# YOTSUBA_GNSS-receiver_Orion_ver_1_5_2.net
KiCad netlist of a schematic drawn in EAGLE
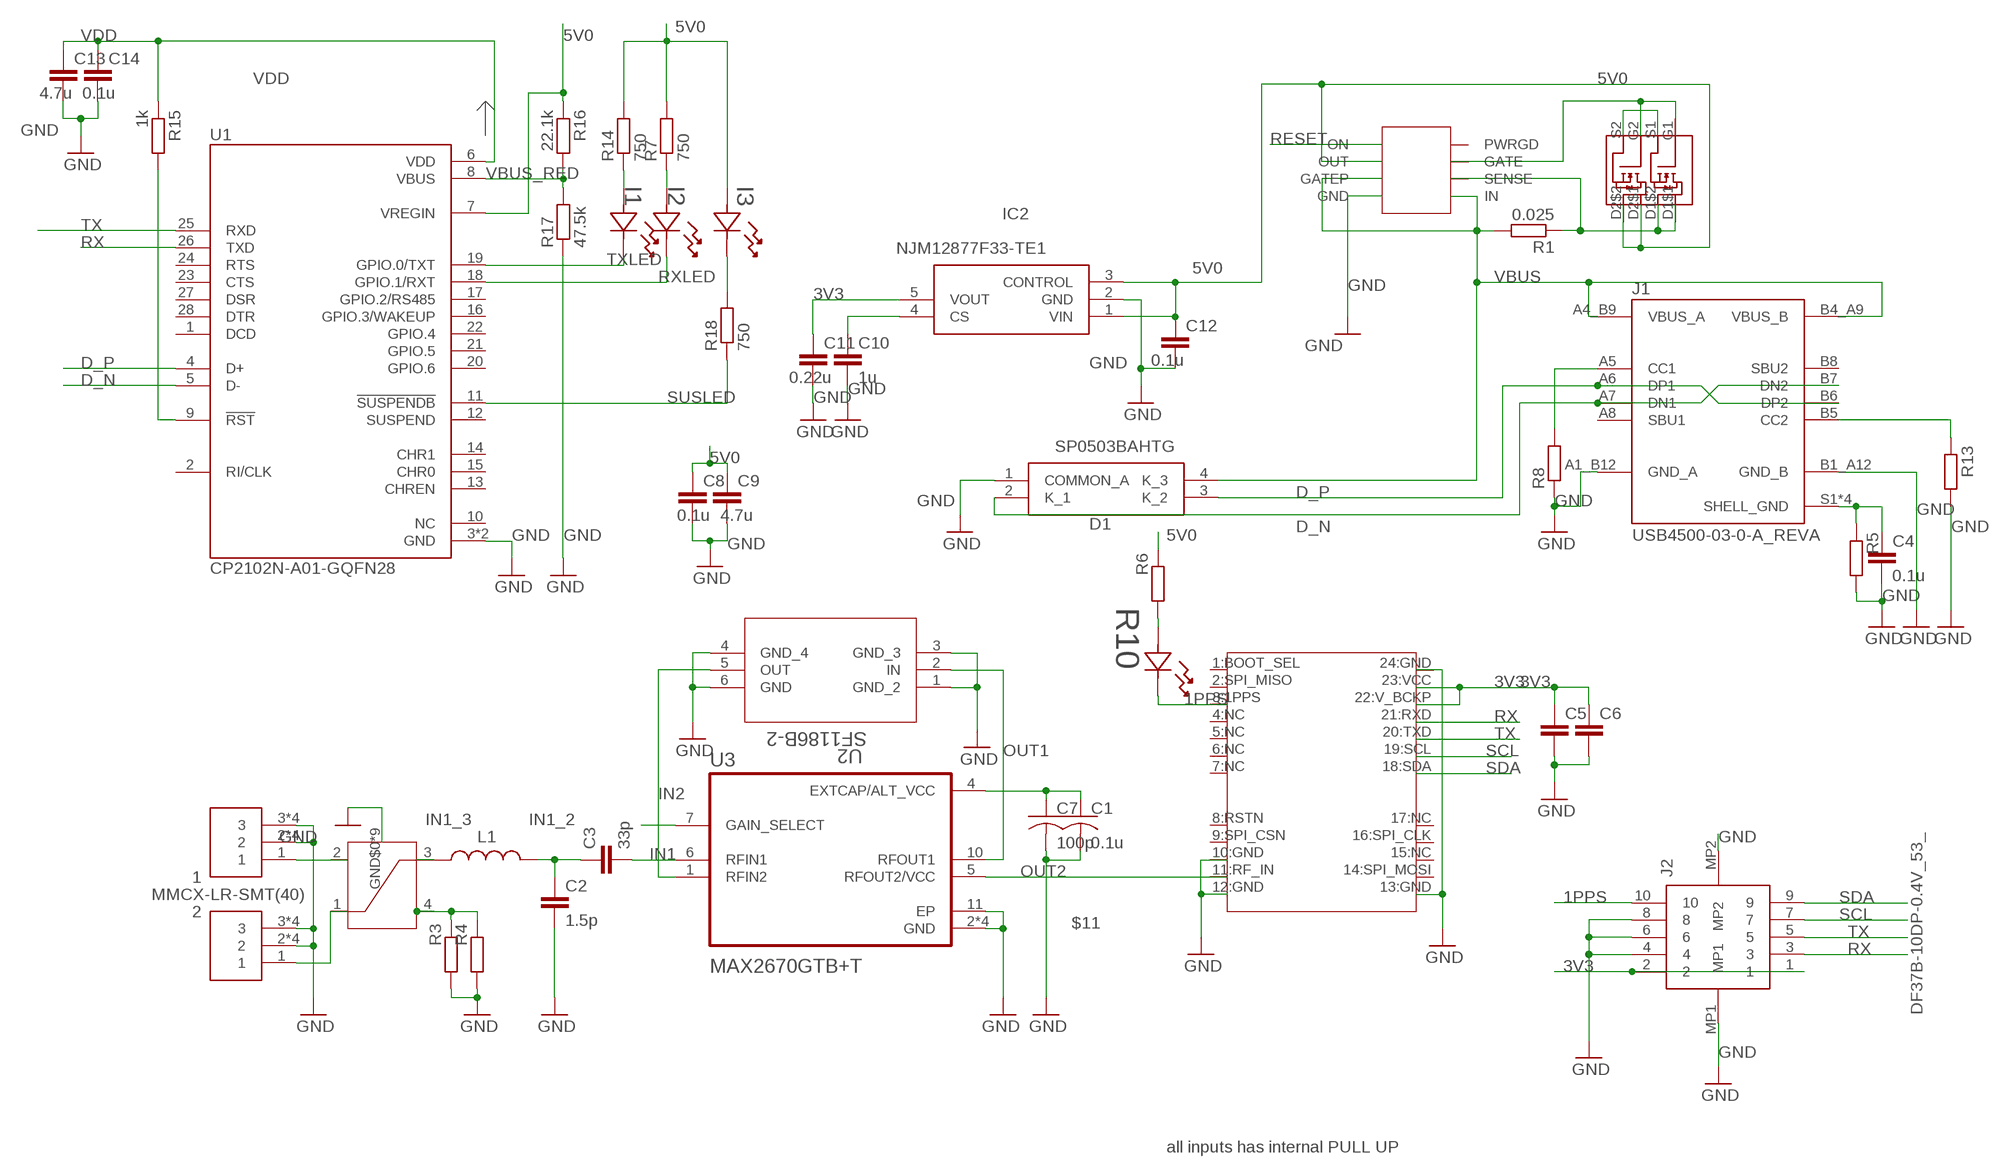
[diagram p0: schematic, sheet 1]

(export (version "E")
  (design (tool "Eeschema 10.0.6"))
  (components
    (comp (ref "1")
      (value "MMCX-LR-SMT(40)")
      (footprint "eagle-import:MMCX-LR-SMT(40)")
      (libsource (lib "eagle-import") (part "MMCX-LR-SMT(40)"))
    )
    (comp (ref "2")
      (value "MMCX-LR-SMT(40)")
      (footprint "eagle-import:MMCX-LR-SMT(40)")
      (libsource (lib "eagle-import") (part "MMCX-LR-SMT(40)"))
    )
    (comp (ref "C1")
      (value "0.1u")
      (footprint "eagle-import:C1608_OS")
      (libsource (lib "eagle-import") (part "C-US"))
    )
    (comp (ref "C2")
      (value "1.5p")
      (footprint "eagle-import:C1608")
      (libsource (lib "eagle-import") (part "C-EUC1608"))
    )
    (comp (ref "C3")
      (value "33p")
      (footprint "eagle-import:C1608")
      (libsource (lib "eagle-import") (part "C-EUC1608"))
    )
    (comp (ref "C4")
      (value "0.1u")
      (footprint "eagle-import:C1608")
      (libsource (lib "eagle-import") (part "C-EUC1608"))
    )
    (comp (ref "C5")
      (value "C-EUC1608")
      (footprint "eagle-import:C1608")
      (libsource (lib "eagle-import") (part "C-EUC1608"))
    )
    (comp (ref "C6")
      (value "C-EUC1608")
      (footprint "eagle-import:C1608")
      (libsource (lib "eagle-import") (part "C-EUC1608"))
    )
    (comp (ref "C7")
      (value "100p")
      (footprint "eagle-import:C1608_OS")
      (libsource (lib "eagle-import") (part "C-US"))
    )
    (comp (ref "C8")
      (value "0.1u")
      (footprint "eagle-import:C1608")
      (libsource (lib "eagle-import") (part "C-EUC1608"))
    )
    (comp (ref "C9")
      (value "4.7u")
      (footprint "eagle-import:C1608")
      (libsource (lib "eagle-import") (part "C-EUC1608"))
    )
    (comp (ref "C10")
      (value "1u")
      (footprint "eagle-import:C1608")
      (libsource (lib "eagle-import") (part "C-EUC1608"))
    )
    (comp (ref "C11")
      (value "0.22u")
      (footprint "eagle-import:C1608")
      (libsource (lib "eagle-import") (part "C-EUC1608"))
    )
    (comp (ref "C12")
      (value "0.1u")
      (footprint "eagle-import:C1608")
      (libsource (lib "eagle-import") (part "C-EUC1608"))
    )
    (comp (ref "C13")
      (value "4.7u")
      (footprint "eagle-import:C1608")
      (libsource (lib "eagle-import") (part "C-EUC1608"))
    )
    (comp (ref "C14")
      (value "0.1u")
      (footprint "eagle-import:C1608")
      (libsource (lib "eagle-import") (part "C-EUC1608"))
    )
    (comp (ref "D1")
      (value "SP0503BAHTG")
      (footprint "eagle-import:SP0503BAHTG")
      (fields (field (name "MOUSER_PART_NUMBER") "576-SP0503BAHTG"))
      (libsource (lib "eagle-import") (part "SP0503BAHTG"))
    )
    (comp (ref "I1")
      (value "SML-E12P8WT86")
      (footprint "eagle-import:LED_SMLD12_ROM")
      (fields (field (name "COPYRIGHT") "Copyright (C) 2023 Ultra Librarian. All rights reserved."))
      (libsource (lib "eagle-import") (part "SML-E12P8WT86"))
    )
    (comp (ref "I2")
      (value "SML-E12P8WT86")
      (footprint "eagle-import:LED_SMLD12_ROM")
      (fields (field (name "COPYRIGHT") "Copyright (C) 2023 Ultra Librarian. All rights reserved."))
      (libsource (lib "eagle-import") (part "SML-E12P8WT86"))
    )
    (comp (ref "I3")
      (value "SML-E12P8WT86")
      (footprint "eagle-import:LED_SMLD12_ROM")
      (fields (field (name "COPYRIGHT") "Copyright (C) 2023 Ultra Librarian. All rights reserved."))
      (libsource (lib "eagle-import") (part "SML-E12P8WT86"))
    )
    (comp (ref "IC2")
      (value "NJM12877F33-TE1")
      (footprint "eagle-import:SOT95P280X120-5N")
      (fields (field (name "MOUSER_PART_NUMBER") "513-NJM12877F33-TE1"))
      (libsource (lib "eagle-import") (part "NJM12877F33-TE1"))
    )
    (comp (ref "J1")
      (value "USB4500-03-0-A_REVA")
      (footprint "eagle-import:GCT_USB4500-03-0-A_REVA")
      (fields
        (field (name "DIGI-KEY_PART_NUMBER") "2073-USB4500-03-0-ATR-ND")
        (field (name "MF") "Global Connector Technology")
        (field (name "MP") "USB4500-03-0-A")
      )
      (libsource (lib "eagle-import") (part "USB4500-03-0-A_REVA"))
    )
    (comp (ref "J2")
      (value "DF37B-10DP-0.4V_53_")
      (footprint "eagle-import:DF37B10DP04V53")
      (fields
        (field (name "MANUFACTURER_PART_NUMBER") "DF37B-10DP-0.4V(53)")
        (field (name "MOUSER_PART_NUMBER") "798-DF37B10DP04V53")
      )
      (libsource (lib "eagle-import") (part "DF37B-10DP-0.4V_53_"))
    )
    (comp (ref "L1")
      (value "LQW18AN4N3C00D")
      (footprint "eagle-import:INDC1608X100N")
      (fields (field (name "DIGIKEY_PART_NUMBER") "490-6896-2-ND") (field (name "MF") "Murata"))
      (libsource (lib "eagle-import") (part "LQW18AN4N3C00D"))
    )
    (comp (ref "R1")
      (value "0.025")
      (footprint "eagle-import:R0603")
      (libsource (lib "eagle-import") (part "R-EU_R0603"))
    )
    (comp (ref "R3")
      (value "R-EU_R0603")
      (footprint "eagle-import:R0603")
      (libsource (lib "eagle-import") (part "R-EU_R0603"))
    )
    (comp (ref "R4")
      (value "R-EU_R0603")
      (footprint "eagle-import:R0603")
      (libsource (lib "eagle-import") (part "R-EU_R0603"))
    )
    (comp (ref "R5")
      (value "R-EU_R0603")
      (footprint "eagle-import:R0603")
      (libsource (lib "eagle-import") (part "R-EU_R0603"))
    )
    (comp (ref "R6")
      (value "R-EU_R0603")
      (footprint "eagle-import:R0603")
      (libsource (lib "eagle-import") (part "R-EU_R0603"))
    )
    (comp (ref "R7")
      (value "750")
      (footprint "eagle-import:R0603")
      (libsource (lib "eagle-import") (part "R-EU_R0603"))
    )
    (comp (ref "R8")
      (value "R-EU_R0603")
      (footprint "eagle-import:R0603")
      (libsource (lib "eagle-import") (part "R-EU_R0603"))
    )
    (comp (ref "R10")
      (value "SML-E12P8WT86")
      (footprint "eagle-import:LED_SMLD12_ROM")
      (fields (field (name "COPYRIGHT") "Copyright (C) 2023 Ultra Librarian. All rights reserved."))
      (libsource (lib "eagle-import") (part "SML-E12P8WT86"))
    )
    (comp (ref "R13")
      (value "R-EU_R0603")
      (footprint "eagle-import:R0603")
      (libsource (lib "eagle-import") (part "R-EU_R0603"))
    )
    (comp (ref "R14")
      (value "750")
      (footprint "eagle-import:R0603")
      (libsource (lib "eagle-import") (part "R-EU_R0603"))
    )
    (comp (ref "R15")
      (value "1k")
      (footprint "eagle-import:R0603")
      (libsource (lib "eagle-import") (part "R-EU_R0603"))
    )
    (comp (ref "R16")
      (value "22.1k")
      (footprint "eagle-import:R0603")
      (libsource (lib "eagle-import") (part "R-EU_R0603"))
    )
    (comp (ref "R17")
      (value "47.5k")
      (footprint "eagle-import:R0603")
      (libsource (lib "eagle-import") (part "R-EU_R0603"))
    )
    (comp (ref "R18")
      (value "750")
      (footprint "eagle-import:R0603")
      (libsource (lib "eagle-import") (part "R-EU_R0603"))
    )
    (comp (ref "U$1")
      (value "ORION_B16")
      (footprint "eagle-import:ORION_B16")
      (libsource (lib "eagle-import") (part "ORION_B16"))
    )
    (comp (ref "U$3")
      (value "HC125.A")
      (footprint "eagle-import:HC125.A")
      (libsource (lib "eagle-import") (part "HC125.A"))
    )
    (comp (ref "U$7")
      (value "DMG6898LSD")
      (footprint "eagle-import:SOIC127P600X150-8N")
      (libsource (lib "eagle-import") (part "DMG6898LSD"))
    )
    (comp (ref "U$8")
      (value "LTC4361")
      (footprint "eagle-import:SOP65P280X100-8N")
      (libsource (lib "eagle-import") (part "LTC4361"))
    )
    (comp (ref "U1")
      (value "CP2102N-A01-GQFN28")
      (footprint "eagle-import:QFN50P500X500X80-29N")
      (fields (field (name "MF") "Silicon Labs"))
      (libsource (lib "eagle-import") (part "CP2102N-A01-GQFN28"))
    )
    (comp (ref "U2")
      (value "SF1186B-2")
      (footprint "eagle-import:SM3030_MUR")
      (fields (field (name "COPYRIGHT") "Copyright (C) 2023 Ultra Librarian. All rights reserved."))
      (libsource (lib "eagle-import") (part "SF1186B-2"))
    )
    (comp (ref "U3")
      (value "MAX2670GTB+T")
      (footprint "eagle-import:DFN300X300X80-11N")
      (fields (field (name "MF") "Analog Devices"))
      (libsource (lib "eagle-import") (part "MAX2670GTB+T"))
    )
  )
  (nets
    (net (code "1") (name "/$11") (class "Default")
      (node (ref "C1") (pin "1") (pinfunction "1_1") (pintype "passive"))
      (node (ref "C7") (pin "1") (pinfunction "1_1") (pintype "passive"))
      (node (ref "U3") (pin "4") (pinfunction "EXTCAP/ALT_VCC_4") (pintype "power_in"))
    )
    (net (code "2") (name "/1PPS") (class "Default")
      (node (ref "J2") (pin "10") (pinfunction "10_10") (pintype "bidirectional"))
      (node (ref "R10") (pin "1") (pinfunction "1_1") (pintype "passive"))
      (node (ref "U$1") (pin "3:1PPS") (pinfunction "3:1PPS_3:1PPS") (pintype "bidirectional"))
    )
    (net (code "3") (name "/3V3") (class "Default")
      (node (ref "C11") (pin "1") (pinfunction "1_1") (pintype "passive"))
      (node (ref "C5") (pin "1") (pinfunction "1_1") (pintype "passive"))
      (node (ref "C6") (pin "1") (pinfunction "1_1") (pintype "passive"))
      (node (ref "IC2") (pin "5") (pinfunction "VOUT_5") (pintype "bidirectional"))
      (node (ref "J2") (pin "1") (pinfunction "1_1") (pintype "bidirectional"))
      (node (ref "J2") (pin "2") (pinfunction "2_2") (pintype "bidirectional"))
      (node (ref "U$1") (pin "22:V_BCKP") (pinfunction "22:V_BCKP_22:V_BCKP") (pintype "bidirectional"))
      (node (ref "U$1") (pin "23:VCC") (pinfunction "23:VCC_23:VCC") (pintype "bidirectional"))
    )
    (net (code "4") (name "/5V0") (class "Default")
      (node (ref "C12") (pin "1") (pinfunction "1_1") (pintype "passive"))
      (node (ref "C8") (pin "1") (pinfunction "1_1") (pintype "passive"))
      (node (ref "C9") (pin "1") (pinfunction "1_1") (pintype "passive"))
      (node (ref "I3") (pin "2") (pinfunction "2_2") (pintype "passive"))
      (node (ref "IC2") (pin "1") (pinfunction "VIN_1") (pintype "bidirectional"))
      (node (ref "IC2") (pin "3") (pinfunction "CONTROL_3") (pintype "bidirectional"))
      (node (ref "R14") (pin "2") (pinfunction "2_2") (pintype "passive"))
      (node (ref "R16") (pin "1") (pinfunction "1_1") (pintype "passive"))
      (node (ref "R6") (pin "2") (pinfunction "2_2") (pintype "passive"))
      (node (ref "R7") (pin "2") (pinfunction "2_2") (pintype "passive"))
      (node (ref "U$7") (pin "D2$1") (pinfunction "D2$1_D2$1") (pintype "bidirectional"))
      (node (ref "U$7") (pin "D2$2") (pinfunction "D2$2_D2$2") (pintype "bidirectional"))
      (node (ref "U$8") (pin "OUT") (pinfunction "OUT_OUT") (pintype "bidirectional"))
      (node (ref "U1") (pin "7") (pinfunction "VREGIN_7") (pintype "power_in"))
    )
    (net (code "5") (name "/D_N") (class "Default")
      (node (ref "D1") (pin "2") (pinfunction "K_1_2") (pintype "bidirectional"))
      (node (ref "J1") (pin "A7") (pinfunction "DN1_A7") (pintype "bidirectional"))
      (node (ref "J1") (pin "B7") (pinfunction "DN2_B7") (pintype "bidirectional"))
      (node (ref "U1") (pin "5") (pinfunction "D-_5") (pintype "bidirectional"))
    )
    (net (code "6") (name "/D_P") (class "Default")
      (node (ref "D1") (pin "3") (pinfunction "K_2_3") (pintype "bidirectional"))
      (node (ref "J1") (pin "A6") (pinfunction "DP1_A6") (pintype "bidirectional"))
      (node (ref "J1") (pin "B6") (pinfunction "DP2_B6") (pintype "bidirectional"))
      (node (ref "U1") (pin "4") (pinfunction "D+_4") (pintype "bidirectional"))
    )
    (net (code "7") (name "/IN1") (class "Default")
      (node (ref "C3") (pin "2") (pinfunction "2_2") (pintype "passive"))
      (node (ref "U3") (pin "6") (pinfunction "RFIN1_6") (pintype "input"))
    )
    (net (code "8") (name "/IN1_2") (class "Default")
      (node (ref "C2") (pin "1") (pinfunction "1_1") (pintype "passive"))
      (node (ref "C3") (pin "1") (pinfunction "1_1") (pintype "passive"))
      (node (ref "L1") (pin "2") (pinfunction "2_2") (pintype "passive"))
    )
    (net (code "9") (name "/IN1_3") (class "Default")
      (node (ref "L1") (pin "1") (pinfunction "1_1") (pintype "passive"))
      (node (ref "U$3") (pin "3") (pinfunction "3_3") (pintype "bidirectional"))
    )
    (net (code "10") (name "/IN2") (class "Default")
      (node (ref "U2") (pin "5") (pinfunction "OUT_5") (pintype "output"))
      (node (ref "U3") (pin "1") (pinfunction "RFIN2_1") (pintype "input"))
    )
    (net (code "11") (name "/OUT1") (class "Default")
      (node (ref "U2") (pin "2") (pinfunction "IN_2") (pintype "input"))
      (node (ref "U3") (pin "10") (pinfunction "RFOUT1_10") (pintype "output"))
    )
    (net (code "12") (name "/OUT2") (class "Default")
      (node (ref "U$1") (pin "11:RF_IN") (pinfunction "11:RF_IN_11:RF_IN") (pintype "bidirectional"))
      (node (ref "U3") (pin "5") (pinfunction "RFOUT2/VCC_5") (pintype "output"))
    )
    (net (code "13") (name "/RESET") (class "Default")
      (node (ref "U$8") (pin "ON") (pinfunction "ON_ON") (pintype "bidirectional"))
    )
    (net (code "14") (name "/RX") (class "Default")
      (node (ref "J2") (pin "3") (pinfunction "3_3") (pintype "bidirectional"))
      (node (ref "U$1") (pin "21:RXD") (pinfunction "21:RXD_21:RXD") (pintype "bidirectional"))
      (node (ref "U1") (pin "26") (pinfunction "TXD_26") (pintype "output"))
    )
    (net (code "15") (name "/RXLED") (class "Default")
      (node (ref "I2") (pin "1") (pinfunction "1_1") (pintype "passive"))
      (node (ref "U1") (pin "18") (pinfunction "GPIO.1/RXT_18") (pintype "bidirectional"))
    )
    (net (code "16") (name "/SCL") (class "Default")
      (node (ref "J2") (pin "7") (pinfunction "7_7") (pintype "bidirectional"))
      (node (ref "U$1") (pin "19:SCL") (pinfunction "19:SCL_19:SCL") (pintype "bidirectional"))
    )
    (net (code "17") (name "/SDA") (class "Default")
      (node (ref "J2") (pin "9") (pinfunction "9_9") (pintype "bidirectional"))
      (node (ref "U$1") (pin "18:SDA") (pinfunction "18:SDA_18:SDA") (pintype "bidirectional"))
    )
    (net (code "18") (name "/SUSLED") (class "Default")
      (node (ref "R18") (pin "1") (pinfunction "1_1") (pintype "passive"))
      (node (ref "U1") (pin "11") (pinfunction "~{SUSPENDB}_11") (pintype "output"))
    )
    (net (code "19") (name "/TX") (class "Default")
      (node (ref "J2") (pin "5") (pinfunction "5_5") (pintype "bidirectional"))
      (node (ref "U$1") (pin "20:TXD") (pinfunction "20:TXD_20:TXD") (pintype "bidirectional"))
      (node (ref "U1") (pin "25") (pinfunction "RXD_25") (pintype "input"))
    )
    (net (code "20") (name "/TXLED") (class "Default")
      (node (ref "I1") (pin "1") (pinfunction "1_1") (pintype "passive"))
      (node (ref "U1") (pin "19") (pinfunction "GPIO.0/TXT_19") (pintype "bidirectional"))
    )
    (net (code "21") (name "/VBUS") (class "Default")
      (node (ref "D1") (pin "4") (pinfunction "K_3_4") (pintype "bidirectional"))
      (node (ref "J1") (pin "A4_B9") (pinfunction "VBUS_A_A4_B9") (pintype "power_in"))
      (node (ref "J1") (pin "B4_A9") (pinfunction "VBUS_B_B4_A9") (pintype "power_in"))
      (node (ref "R1") (pin "2") (pinfunction "2_2") (pintype "passive"))
      (node (ref "U$8") (pin "GATEP") (pinfunction "GATEP_GATEP") (pintype "bidirectional"))
      (node (ref "U$8") (pin "IN") (pinfunction "IN_IN") (pintype "bidirectional"))
    )
    (net (code "22") (name "/VBUS_RED") (class "Default")
      (node (ref "R16") (pin "2") (pinfunction "2_2") (pintype "passive"))
      (node (ref "R17") (pin "2") (pinfunction "2_2") (pintype "passive"))
      (node (ref "U1") (pin "8") (pinfunction "VBUS_8") (pintype "power_in"))
    )
    (net (code "23") (name "/VDD") (class "Default")
      (node (ref "C13") (pin "1") (pinfunction "1_1") (pintype "passive"))
      (node (ref "C14") (pin "1") (pinfunction "1_1") (pintype "passive"))
      (node (ref "R15") (pin "1") (pinfunction "1_1") (pintype "passive"))
      (node (ref "U1") (pin "6") (pinfunction "VDD_6") (pintype "power_in"))
    )
    (net (code "24") (name "GND") (class "Default")
      (node (ref "1") (pin "2") (pinfunction "2_2") (pintype "bidirectional"))
      (node (ref "1") (pin "3") (pinfunction "3_3") (pintype "bidirectional"))
      (node (ref "1") (pin "4") (pinfunction "2_4") (pintype "bidirectional"))
      (node (ref "1") (pin "5") (pinfunction "3_5") (pintype "bidirectional"))
      (node (ref "1") (pin "P$1") (pinfunction "2_P$1") (pintype "bidirectional"))
      (node (ref "1") (pin "P$2") (pinfunction "2_P$2") (pintype "bidirectional"))
      (node (ref "1") (pin "P$3") (pinfunction "3_P$3") (pintype "bidirectional"))
      (node (ref "1") (pin "P$4") (pinfunction "3_P$4") (pintype "bidirectional"))
      (node (ref "2") (pin "2") (pinfunction "2_2") (pintype "bidirectional"))
      (node (ref "2") (pin "3") (pinfunction "3_3") (pintype "bidirectional"))
      (node (ref "2") (pin "4") (pinfunction "2_4") (pintype "bidirectional"))
      (node (ref "2") (pin "5") (pinfunction "3_5") (pintype "bidirectional"))
      (node (ref "2") (pin "P$1") (pinfunction "2_P$1") (pintype "bidirectional"))
      (node (ref "2") (pin "P$2") (pinfunction "2_P$2") (pintype "bidirectional"))
      (node (ref "2") (pin "P$3") (pinfunction "3_P$3") (pintype "bidirectional"))
      (node (ref "2") (pin "P$4") (pinfunction "3_P$4") (pintype "bidirectional"))
      (node (ref "C1") (pin "2") (pinfunction "2_2") (pintype "passive"))
      (node (ref "C10") (pin "2") (pinfunction "2_2") (pintype "passive"))
      (node (ref "C11") (pin "2") (pinfunction "2_2") (pintype "passive"))
      (node (ref "C12") (pin "2") (pinfunction "2_2") (pintype "passive"))
      (node (ref "C13") (pin "2") (pinfunction "2_2") (pintype "passive"))
      (node (ref "C14") (pin "2") (pinfunction "2_2") (pintype "passive"))
      (node (ref "C2") (pin "2") (pinfunction "2_2") (pintype "passive"))
      (node (ref "C4") (pin "2") (pinfunction "2_2") (pintype "passive"))
      (node (ref "C5") (pin "2") (pinfunction "2_2") (pintype "passive"))
      (node (ref "C6") (pin "2") (pinfunction "2_2") (pintype "passive"))
      (node (ref "C7") (pin "2") (pinfunction "2_2") (pintype "passive"))
      (node (ref "C8") (pin "2") (pinfunction "2_2") (pintype "passive"))
      (node (ref "C9") (pin "2") (pinfunction "2_2") (pintype "passive"))
      (node (ref "D1") (pin "1") (pinfunction "COMMON_A_1") (pintype "bidirectional"))
      (node (ref "IC2") (pin "2") (pinfunction "GND_2") (pintype "bidirectional"))
      (node (ref "J1") (pin "A1_B12") (pinfunction "GND_A_A1_B12") (pintype "power_in"))
      (node (ref "J1") (pin "B1_A12") (pinfunction "GND_B_B1_A12") (pintype "power_in"))
      (node (ref "J2") (pin "4") (pinfunction "4_4") (pintype "bidirectional"))
      (node (ref "J2") (pin "6") (pinfunction "6_6") (pintype "bidirectional"))
      (node (ref "J2") (pin "8") (pinfunction "8_8") (pintype "bidirectional"))
      (node (ref "J2") (pin "MP1") (pinfunction "MP1_MP1") (pintype "bidirectional"))
      (node (ref "J2") (pin "MP2") (pinfunction "MP2_MP2") (pintype "bidirectional"))
      (node (ref "R13") (pin "2") (pinfunction "2_2") (pintype "passive"))
      (node (ref "R17") (pin "1") (pinfunction "1_1") (pintype "passive"))
      (node (ref "R3") (pin "1") (pinfunction "1_1") (pintype "passive"))
      (node (ref "R4") (pin "1") (pinfunction "1_1") (pintype "passive"))
      (node (ref "R5") (pin "2") (pinfunction "2_2") (pintype "passive"))
      (node (ref "R8") (pin "1") (pinfunction "1_1") (pintype "passive"))
      (node (ref "U$1") (pin "10:GND") (pinfunction "10:GND_10:GND") (pintype "bidirectional"))
      (node (ref "U$1") (pin "12:GND") (pinfunction "12:GND_12:GND") (pintype "bidirectional"))
      (node (ref "U$1") (pin "13:GND") (pinfunction "13:GND_13:GND") (pintype "bidirectional"))
      (node (ref "U$1") (pin "24:GND") (pinfunction "24:GND_24:GND") (pintype "bidirectional"))
      (node (ref "U$3") (pin "GND$0") (pinfunction "GND_GND$0") (pintype "bidirectional"))
      (node (ref "U$3") (pin "GND$1") (pinfunction "GND_GND$1") (pintype "bidirectional"))
      (node (ref "U$3") (pin "GND$2") (pinfunction "GND_GND$2") (pintype "bidirectional"))
      (node (ref "U$3") (pin "GND$3") (pinfunction "GND_GND$3") (pintype "bidirectional"))
      (node (ref "U$3") (pin "GND$4") (pinfunction "GND_GND$4") (pintype "bidirectional"))
      (node (ref "U$3") (pin "GND$5") (pinfunction "GND_GND$5") (pintype "bidirectional"))
      (node (ref "U$3") (pin "GND$6") (pinfunction "GND_GND$6") (pintype "bidirectional"))
      (node (ref "U$3") (pin "GND$7") (pinfunction "GND_GND$7") (pintype "bidirectional"))
      (node (ref "U$3") (pin "GND$8") (pinfunction "GND_GND$8") (pintype "bidirectional"))
      (node (ref "U$8") (pin "GND") (pinfunction "GND_GND") (pintype "bidirectional"))
      (node (ref "U1") (pin "29") (pinfunction "GND_29") (pintype "power_in"))
      (node (ref "U1") (pin "3") (pinfunction "GND_3") (pintype "power_in"))
      (node (ref "U2") (pin "1") (pinfunction "GND_2_1") (pintype "passive"))
      (node (ref "U2") (pin "3") (pinfunction "GND_3_3") (pintype "passive"))
      (node (ref "U2") (pin "4") (pinfunction "GND_4_4") (pintype "passive"))
      (node (ref "U2") (pin "6") (pinfunction "GND_6") (pintype "passive"))
      (node (ref "U3") (pin "11") (pinfunction "EP_11") (pintype "power_in"))
      (node (ref "U3") (pin "2") (pinfunction "GND_2") (pintype "power_in"))
      (node (ref "U3") (pin "3") (pinfunction "GND_3") (pintype "power_in"))
      (node (ref "U3") (pin "8") (pinfunction "GND_8") (pintype "power_in"))
      (node (ref "U3") (pin "9") (pinfunction "GND_9") (pintype "power_in"))
    )
    (net (code "25") (name "Net-(1-Pad1)") (class "Default")
      (node (ref "1") (pin "1") (pinfunction "1_1") (pintype "bidirectional"))
      (node (ref "U$3") (pin "2") (pinfunction "2_2") (pintype "bidirectional"))
    )
    (net (code "26") (name "Net-(2-Pad1)") (class "Default")
      (node (ref "2") (pin "1") (pinfunction "1_1") (pintype "bidirectional"))
      (node (ref "U$3") (pin "1") (pinfunction "1_1") (pintype "bidirectional"))
    )
    (net (code "27") (name "Net-(C4-Pad1)") (class "Default")
      (node (ref "C4") (pin "1") (pinfunction "1_1") (pintype "passive"))
      (node (ref "J1") (pin "S1") (pinfunction "SHELL_GND_S1") (pintype "power_in"))
      (node (ref "J1") (pin "S2") (pinfunction "SHELL_GND_S2") (pintype "power_in"))
      (node (ref "J1") (pin "S3") (pinfunction "SHELL_GND_S3") (pintype "power_in"))
      (node (ref "J1") (pin "S4") (pinfunction "SHELL_GND_S4") (pintype "power_in"))
      (node (ref "R5") (pin "1") (pinfunction "1_1") (pintype "passive"))
    )
    (net (code "28") (name "Net-(I1-Pad2)") (class "Default")
      (node (ref "I1") (pin "2") (pinfunction "2_2") (pintype "passive"))
      (node (ref "R14") (pin "1") (pinfunction "1_1") (pintype "passive"))
    )
    (net (code "29") (name "Net-(I2-Pad2)") (class "Default")
      (node (ref "I2") (pin "2") (pinfunction "2_2") (pintype "passive"))
      (node (ref "R7") (pin "1") (pinfunction "1_1") (pintype "passive"))
    )
    (net (code "30") (name "Net-(I3-Pad1)") (class "Default")
      (node (ref "I3") (pin "1") (pinfunction "1_1") (pintype "passive"))
      (node (ref "R18") (pin "2") (pinfunction "2_2") (pintype "passive"))
    )
    (net (code "31") (name "Net-(IC2-CS)") (class "Default")
      (node (ref "C10") (pin "1") (pinfunction "1_1") (pintype "passive"))
      (node (ref "IC2") (pin "4") (pinfunction "CS_4") (pintype "bidirectional"))
    )
    (net (code "32") (name "Net-(J1-CC1)") (class "Default")
      (node (ref "J1") (pin "A5") (pinfunction "CC1_A5") (pintype "bidirectional"))
      (node (ref "R8") (pin "2") (pinfunction "2_2") (pintype "passive"))
    )
    (net (code "33") (name "Net-(J1-CC2)") (class "Default")
      (node (ref "J1") (pin "B5") (pinfunction "CC2_B5") (pintype "bidirectional"))
      (node (ref "R13") (pin "1") (pinfunction "1_1") (pintype "passive"))
    )
    (net (code "34") (name "Net-(R1-Pad1)") (class "Default")
      (node (ref "R1") (pin "1") (pinfunction "1_1") (pintype "passive"))
      (node (ref "U$7") (pin "D1$1") (pinfunction "D1$1_D1$1") (pintype "bidirectional"))
      (node (ref "U$7") (pin "D1$2") (pinfunction "D1$2_D1$2") (pintype "bidirectional"))
      (node (ref "U$8") (pin "SENSE") (pinfunction "SENSE_SENSE") (pintype "bidirectional"))
    )
    (net (code "35") (name "Net-(R3-Pad2)") (class "Default")
      (node (ref "R3") (pin "2") (pinfunction "2_2") (pintype "passive"))
      (node (ref "R4") (pin "2") (pinfunction "2_2") (pintype "passive"))
      (node (ref "U$3") (pin "4") (pinfunction "4_4") (pintype "bidirectional"))
    )
    (net (code "36") (name "Net-(R10-Pad2)") (class "Default")
      (node (ref "R10") (pin "2") (pinfunction "2_2") (pintype "passive"))
      (node (ref "R6") (pin "1") (pinfunction "1_1") (pintype "passive"))
    )
    (net (code "37") (name "Net-(U$7-PadG1)") (class "Default")
      (node (ref "U$7") (pin "G1") (pinfunction "G1_G1") (pintype "bidirectional"))
      (node (ref "U$7") (pin "G2") (pinfunction "G2_G2") (pintype "bidirectional"))
      (node (ref "U$8") (pin "GATE") (pinfunction "GATE_GATE") (pintype "bidirectional"))
    )
    (net (code "38") (name "Net-(U$7-PadS1)") (class "Default")
      (node (ref "U$7") (pin "S1") (pinfunction "S1_S1") (pintype "bidirectional"))
      (node (ref "U$7") (pin "S2") (pinfunction "S2_S2") (pintype "bidirectional"))
    )
    (net (code "39") (name "Net-(U1-~{RST})") (class "Default")
      (node (ref "R15") (pin "2") (pinfunction "2_2") (pintype "passive"))
      (node (ref "U1") (pin "9") (pinfunction "~{RST}_9") (pintype "input"))
    )
    (net (code "40") (name "unconnected-(J1-SBU1-PadA8)") (class "Default")
      (node (ref "J1") (pin "A8") (pinfunction "SBU1_A8") (pintype "bidirectional"))
    )
    (net (code "41") (name "unconnected-(J1-SBU2-PadB8)") (class "Default")
      (node (ref "J1") (pin "B8") (pinfunction "SBU2_B8") (pintype "bidirectional"))
    )
    (net (code "42") (name "unconnected-(U$1-Pad1:BOOT_SEL)") (class "Default")
      (node (ref "U$1") (pin "1:BOOT_SEL") (pinfunction "1:BOOT_SEL_1:BOOT_SEL") (pintype "bidirectional"))
    )
    (net (code "43") (name "unconnected-(U$1-Pad2:SPI_MISO)") (class "Default")
      (node (ref "U$1") (pin "2:SPI_MISO") (pinfunction "2:SPI_MISO_2:SPI_MISO") (pintype "bidirectional"))
    )
    (net (code "44") (name "unconnected-(U$1-Pad4:NC)") (class "Default")
      (node (ref "U$1") (pin "4:NC") (pinfunction "4:NC_4:NC") (pintype "bidirectional"))
    )
    (net (code "45") (name "unconnected-(U$1-Pad5:NC)") (class "Default")
      (node (ref "U$1") (pin "5:NC") (pinfunction "5:NC_5:NC") (pintype "bidirectional"))
    )
    (net (code "46") (name "unconnected-(U$1-Pad6:NC)") (class "Default")
      (node (ref "U$1") (pin "6:NC") (pinfunction "6:NC_6:NC") (pintype "bidirectional"))
    )
    (net (code "47") (name "unconnected-(U$1-Pad7:NC)") (class "Default")
      (node (ref "U$1") (pin "7:NC") (pinfunction "7:NC_7:NC") (pintype "bidirectional"))
    )
    (net (code "48") (name "unconnected-(U$1-Pad8:RSTN)") (class "Default")
      (node (ref "U$1") (pin "8:RSTN") (pinfunction "8:RSTN_8:RSTN") (pintype "bidirectional"))
    )
    (net (code "49") (name "unconnected-(U$1-Pad9:SPI_CSN)") (class "Default")
      (node (ref "U$1") (pin "9:SPI_CSN") (pinfunction "9:SPI_CSN_9:SPI_CSN") (pintype "bidirectional"))
    )
    (net (code "50") (name "unconnected-(U$1-Pad14:SPI_MOSI)") (class "Default")
      (node (ref "U$1") (pin "14:SPI_MOSI") (pinfunction "14:SPI_MOSI_14:SPI_MOSI") (pintype "bidirectional"))
    )
    (net (code "51") (name "unconnected-(U$1-Pad15:NC)") (class "Default")
      (node (ref "U$1") (pin "15:NC") (pinfunction "15:NC_15:NC") (pintype "bidirectional"))
    )
    (net (code "52") (name "unconnected-(U$1-Pad16:SPI_CLK)") (class "Default")
      (node (ref "U$1") (pin "16:SPI_CLK") (pinfunction "16:SPI_CLK_16:SPI_CLK") (pintype "bidirectional"))
    )
    (net (code "53") (name "unconnected-(U$1-Pad17:NC)") (class "Default")
      (node (ref "U$1") (pin "17:NC") (pinfunction "17:NC_17:NC") (pintype "bidirectional"))
    )
    (net (code "54") (name "unconnected-(U$8-PadPWRGD)") (class "Default")
      (node (ref "U$8") (pin "PWRGD") (pinfunction "PWRGD_PWRGD") (pintype "bidirectional"))
    )
    (net (code "55") (name "unconnected-(U1-CHR0-Pad15)") (class "Default")
      (node (ref "U1") (pin "15") (pinfunction "CHR0_15") (pintype "output"))
    )
    (net (code "56") (name "unconnected-(U1-CHR1-Pad14)") (class "Default")
      (node (ref "U1") (pin "14") (pinfunction "CHR1_14") (pintype "output"))
    )
    (net (code "57") (name "unconnected-(U1-CHREN-Pad13)") (class "Default")
      (node (ref "U1") (pin "13") (pinfunction "CHREN_13") (pintype "output"))
    )
    (net (code "58") (name "unconnected-(U1-CTS-Pad23)") (class "Default")
      (node (ref "U1") (pin "23") (pinfunction "CTS_23") (pintype "input"))
    )
    (net (code "59") (name "unconnected-(U1-DCD-Pad1)") (class "Default")
      (node (ref "U1") (pin "1") (pinfunction "DCD_1") (pintype "input"))
    )
    (net (code "60") (name "unconnected-(U1-DSR-Pad27)") (class "Default")
      (node (ref "U1") (pin "27") (pinfunction "DSR_27") (pintype "input"))
    )
    (net (code "61") (name "unconnected-(U1-DTR-Pad28)") (class "Default")
      (node (ref "U1") (pin "28") (pinfunction "DTR_28") (pintype "output"))
    )
    (net (code "62") (name "unconnected-(U1-GPIO.2{slash}RS485-Pad17)") (class "Default")
      (node (ref "U1") (pin "17") (pinfunction "GPIO.2/RS485_17") (pintype "bidirectional"))
    )
    (net (code "63") (name "unconnected-(U1-GPIO.3{slash}WAKEUP-Pad16)") (class "Default")
      (node (ref "U1") (pin "16") (pinfunction "GPIO.3/WAKEUP_16") (pintype "bidirectional"))
    )
    (net (code "64") (name "unconnected-(U1-GPIO.4-Pad22)") (class "Default")
      (node (ref "U1") (pin "22") (pinfunction "GPIO.4_22") (pintype "bidirectional"))
    )
    (net (code "65") (name "unconnected-(U1-GPIO.5-Pad21)") (class "Default")
      (node (ref "U1") (pin "21") (pinfunction "GPIO.5_21") (pintype "bidirectional"))
    )
    (net (code "66") (name "unconnected-(U1-GPIO.6-Pad20)") (class "Default")
      (node (ref "U1") (pin "20") (pinfunction "GPIO.6_20") (pintype "bidirectional"))
    )
    (net (code "67") (name "unconnected-(U1-NC-Pad10)") (class "Default")
      (node (ref "U1") (pin "10") (pinfunction "NC_10") (pintype "no_connect"))
    )
    (net (code "68") (name "unconnected-(U1-RI{slash}CLK-Pad2)") (class "Default")
      (node (ref "U1") (pin "2") (pinfunction "RI/CLK_2") (pintype "bidirectional"))
    )
    (net (code "69") (name "unconnected-(U1-RTS-Pad24)") (class "Default")
      (node (ref "U1") (pin "24") (pinfunction "RTS_24") (pintype "output"))
    )
    (net (code "70") (name "unconnected-(U1-SUSPEND-Pad12)") (class "Default")
      (node (ref "U1") (pin "12") (pinfunction "SUSPEND_12") (pintype "output"))
    )
    (net (code "71") (name "unconnected-(U3-GAIN_SELECT-Pad7)") (class "Default")
      (node (ref "U3") (pin "7") (pinfunction "GAIN_SELECT_7") (pintype "input"))
    )
  )
)
